# Rauchmelder_2_1.net
KiCad netlist of a schematic drawn in EAGLE
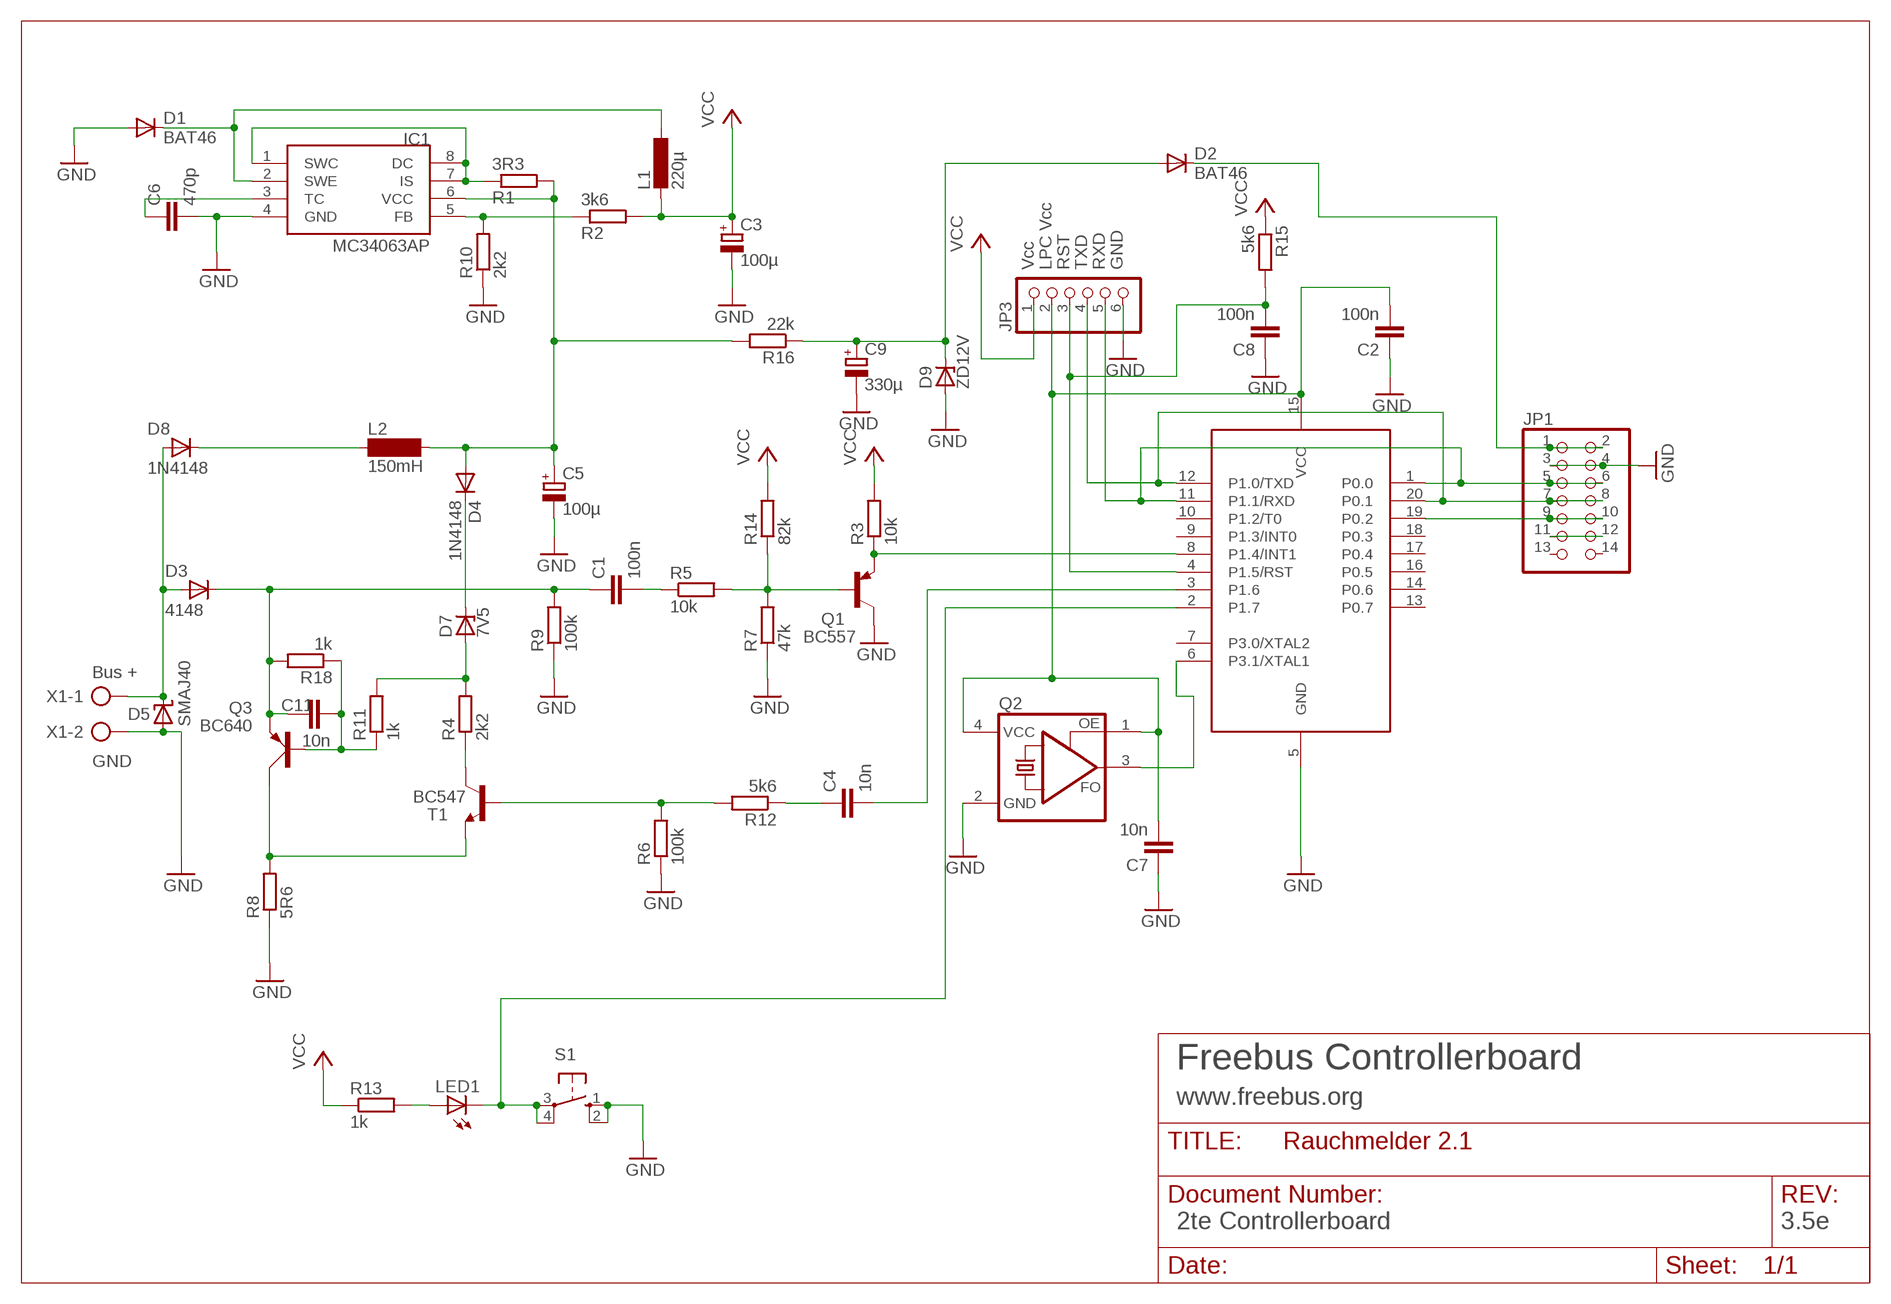
[diagram p0: schematic, sheet 1]

(export (version "E")
  (design (tool "Eeschema 10.0.6"))
  (components
    (comp (ref "89LPC922")
      (value "89LPC922")
      (footprint "eagle-import:DIL20")
      (libsource (lib "eagle-import") (part "89LPC922"))
    )
    (comp (ref "C1")
      (value "100n")
      (footprint "eagle-import:C025-024X044")
      (libsource (lib "eagle-import") (part "C-EU025-024X044"))
    )
    (comp (ref "C2")
      (value "100n")
      (footprint "eagle-import:C025-024X044")
      (libsource (lib "eagle-import") (part "C-EU025-024X044"))
    )
    (comp (ref "C3")
      (value "100µ")
      (footprint "eagle-import:E2,5-6")
      (libsource (lib "eagle-import") (part "CPOL-EUE2.5-6"))
    )
    (comp (ref "C4")
      (value "10n")
      (footprint "eagle-import:C025-024X044")
      (libsource (lib "eagle-import") (part "C-EU025-024X044"))
    )
    (comp (ref "C5")
      (value "100µ")
      (footprint "eagle-import:E3,5-8")
      (libsource (lib "eagle-import") (part "CPOL-EUE3.5-8"))
    )
    (comp (ref "C6")
      (value "470p")
      (footprint "eagle-import:C025-024X044")
      (libsource (lib "eagle-import") (part "C-EU025-024X044"))
    )
    (comp (ref "C7")
      (value "10n")
      (footprint "eagle-import:C1206")
      (libsource (lib "eagle-import") (part "C-EUC1206"))
    )
    (comp (ref "C8")
      (value "100n")
      (footprint "eagle-import:C025-024X044")
      (libsource (lib "eagle-import") (part "C-EU025-024X044"))
    )
    (comp (ref "C9")
      (value "330µ")
      (footprint "eagle-import:E3,5-8")
      (libsource (lib "eagle-import") (part "CPOL-EUE3.5-8"))
    )
    (comp (ref "C11")
      (value "10n")
      (footprint "eagle-import:C025-024X044")
      (libsource (lib "eagle-import") (part "C-EU025-024X044"))
    )
    (comp (ref "D1")
      (value "BAT46")
      (footprint "eagle-import:DO34-7")
      (libsource (lib "eagle-import") (part "BAT81"))
    )
    (comp (ref "D2")
      (value "BAT46")
      (footprint "eagle-import:DO34-7")
      (libsource (lib "eagle-import") (part "BAT81"))
    )
    (comp (ref "D3")
      (value "4148")
      (footprint "eagle-import:DO35-S")
      (libsource (lib "eagle-import") (part "DO35-STEHEND"))
    )
    (comp (ref "D4")
      (value "1N4148")
      (footprint "eagle-import:DO35-10")
      (libsource (lib "eagle-import") (part "1N4148"))
    )
    (comp (ref "D5")
      (value "SMAJ40")
      (footprint "eagle-import:SMBJ")
      (libsource (lib "eagle-import") (part "SUPPRESSOR-SMBJ"))
    )
    (comp (ref "D7")
      (value "7V5")
      (footprint "eagle-import:ZDIO-2.5")
      (libsource (lib "eagle-import") (part "BZX85ZDIOV"))
    )
    (comp (ref "D8")
      (value "1N4148")
      (footprint "eagle-import:DO35-S")
      (libsource (lib "eagle-import") (part "DO35-STEHEND"))
    )
    (comp (ref "D9")
      (value "ZD12V")
      (footprint "eagle-import:DO34Z7")
      (libsource (lib "eagle-import") (part "BZX90"))
    )
    (comp (ref "IC1")
      (value "MC34063AP")
      (footprint "eagle-import:DIL08")
      (libsource (lib "eagle-import") (part "MC34063AP"))
    )
    (comp (ref "JP1")
      (value "PINHD-2X7")
      (footprint "eagle-import:2X07")
      (libsource (lib "eagle-import") (part "PINHD-2X7"))
    )
    (comp (ref "JP3")
      (value "PINHD-1X6")
      (footprint "eagle-import:1X06")
      (libsource (lib "eagle-import") (part "PINHD-1X6"))
    )
    (comp (ref "L1")
      (value "220µ")
      (footprint "eagle-import:0207_12")
      (libsource (lib "eagle-import") (part "L-EU0207/12"))
    )
    (comp (ref "L2")
      (value "150mH")
      (footprint "eagle-import:BS11")
      (libsource (lib "eagle-import") (part "BS11"))
    )
    (comp (ref "LED1")
      (value "LED3MM")
      (footprint "eagle-import:LED3MM")
      (libsource (lib "eagle-import") (part "LED3MM"))
    )
    (comp (ref "Q1")
      (value "BC557")
      (footprint "eagle-import:TO92")
      (libsource (lib "eagle-import") (part "BC557"))
    )
    (comp (ref "Q2")
      (value "ASFL")
      (footprint "eagle-import:ASF")
      (libsource (lib "eagle-import") (part "ASFL"))
    )
    (comp (ref "Q3")
      (value "BC640")
      (footprint "eagle-import:SOT54D")
      (libsource (lib "eagle-import") (part "BC640"))
    )
    (comp (ref "R1")
      (value "3R3")
      (footprint "eagle-import:0207_7")
      (libsource (lib "eagle-import") (part "R-EU_0207/7"))
    )
    (comp (ref "R2")
      (value "3k6")
      (footprint "eagle-import:0207_7")
      (libsource (lib "eagle-import") (part "R-EU_0207/7"))
    )
    (comp (ref "R3")
      (value "10k")
      (footprint "eagle-import:0207_7")
      (libsource (lib "eagle-import") (part "R-EU_0207/7"))
    )
    (comp (ref "R4")
      (value "2k2")
      (footprint "eagle-import:0207_2V")
      (libsource (lib "eagle-import") (part "R-EU_0207/2V"))
    )
    (comp (ref "R5")
      (value "10k")
      (footprint "eagle-import:0207_7")
      (libsource (lib "eagle-import") (part "R-EU_0207/7"))
    )
    (comp (ref "R6")
      (value "100k")
      (footprint "eagle-import:0207_2V")
      (libsource (lib "eagle-import") (part "R-EU_0207/2V"))
    )
    (comp (ref "R7")
      (value "47k")
      (footprint "eagle-import:0207_7")
      (libsource (lib "eagle-import") (part "R-EU_0207/7"))
    )
    (comp (ref "R8")
      (value "5R6")
      (footprint "eagle-import:0207_2V")
      (libsource (lib "eagle-import") (part "R-EU_0207/2V"))
    )
    (comp (ref "R9")
      (value "100k")
      (footprint "eagle-import:0207_7")
      (libsource (lib "eagle-import") (part "R-EU_0207/7"))
    )
    (comp (ref "R10")
      (value "2k2")
      (footprint "eagle-import:0207_7")
      (libsource (lib "eagle-import") (part "R-EU_0207/7"))
    )
    (comp (ref "R11")
      (value "1k")
      (footprint "eagle-import:0207_2V")
      (libsource (lib "eagle-import") (part "R-EU_0207/2V"))
    )
    (comp (ref "R12")
      (value "5k6")
      (footprint "eagle-import:0207_7")
      (libsource (lib "eagle-import") (part "R-EU_0207/7"))
    )
    (comp (ref "R13")
      (value "1k")
      (footprint "eagle-import:0207_7")
      (libsource (lib "eagle-import") (part "R-EU_0207/7"))
    )
    (comp (ref "R14")
      (value "82k")
      (footprint "eagle-import:0207_7")
      (libsource (lib "eagle-import") (part "R-EU_0207/7"))
    )
    (comp (ref "R15")
      (value "5k6")
      (footprint "eagle-import:0207_2V")
      (libsource (lib "eagle-import") (part "R-EU_0207/2V"))
    )
    (comp (ref "R16")
      (value "22k")
      (footprint "eagle-import:0207_2V")
      (libsource (lib "eagle-import") (part "R-EU_0207/2V"))
    )
    (comp (ref "R18")
      (value "1k")
      (footprint "eagle-import:0207_2V")
      (libsource (lib "eagle-import") (part "R-EU_0207/2V"))
    )
    (comp (ref "S1")
      (value "10-XX")
      (footprint "eagle-import:B3F-10XX")
      (libsource (lib "eagle-import") (part "10-XX"))
    )
    (comp (ref "T1")
      (value "BC547")
      (footprint "eagle-import:TO92")
      (libsource (lib "eagle-import") (part "BC547"))
    )
    (comp (ref "X1")
      (value "AK500/2")
      (footprint "eagle-import:AK500_2")
      (libsource (lib "eagle-import") (part "AK500/2"))
    )
  )
  (nets
    (net (code "1") (name "GND") (class "Default")
      (node (ref "89LPC922") (pin "5") (pinfunction "GND_5") (pintype "bidirectional"))
      (node (ref "C2") (pin "1") (pinfunction "1_1") (pintype "passive"))
      (node (ref "C3") (pin "-") (pinfunction "-_-") (pintype "passive"))
      (node (ref "C5") (pin "-") (pinfunction "-_-") (pintype "passive"))
      (node (ref "C6") (pin "2") (pinfunction "2_2") (pintype "passive"))
      (node (ref "C7") (pin "1") (pinfunction "1_1") (pintype "passive"))
      (node (ref "C8") (pin "1") (pinfunction "1_1") (pintype "passive"))
      (node (ref "C9") (pin "-") (pinfunction "-_-") (pintype "passive"))
      (node (ref "D1") (pin "A") (pinfunction "A_A") (pintype "passive"))
      (node (ref "D5") (pin "A") (pinfunction "A_A") (pintype "passive"))
      (node (ref "D9") (pin "A") (pinfunction "A_A") (pintype "passive"))
      (node (ref "IC1") (pin "4") (pinfunction "GND_4") (pintype "passive"))
      (node (ref "JP1") (pin "3") (pinfunction "3_3") (pintype "passive"))
      (node (ref "JP1") (pin "4") (pinfunction "4_4") (pintype "passive"))
      (node (ref "JP3") (pin "6") (pinfunction "6_6") (pintype "passive"))
      (node (ref "Q1") (pin "3") (pinfunction "C_3") (pintype "passive"))
      (node (ref "Q2") (pin "2") (pinfunction "GND_2") (pintype "power_in"))
      (node (ref "R10") (pin "1") (pinfunction "1_1") (pintype "passive"))
      (node (ref "R6") (pin "1") (pinfunction "1_1") (pintype "passive"))
      (node (ref "R7") (pin "1") (pinfunction "1_1") (pintype "passive"))
      (node (ref "R8") (pin "1") (pinfunction "1_1") (pintype "passive"))
      (node (ref "R9") (pin "1") (pinfunction "1_1") (pintype "passive"))
      (node (ref "S1") (pin "1") (pinfunction "S_1") (pintype "passive"))
      (node (ref "S1") (pin "2") (pinfunction "S1_2") (pintype "passive"))
      (node (ref "X1") (pin "2") (pinfunction "KL_2") (pintype "passive"))
    )
    (net (code "2") (name "Net-(89LPC922-P0.0)") (class "Default")
      (node (ref "89LPC922") (pin "1") (pinfunction "P0.0_1") (pintype "bidirectional"))
      (node (ref "89LPC922") (pin "11") (pinfunction "P1.1/RXD_11") (pintype "bidirectional"))
      (node (ref "JP1") (pin "5") (pinfunction "5_5") (pintype "passive"))
      (node (ref "JP1") (pin "6") (pinfunction "6_6") (pintype "passive"))
      (node (ref "JP3") (pin "5") (pinfunction "5_5") (pintype "passive"))
    )
    (net (code "3") (name "Net-(89LPC922-P0.1)") (class "Default")
      (node (ref "89LPC922") (pin "12") (pinfunction "P1.0/TXD_12") (pintype "bidirectional"))
      (node (ref "89LPC922") (pin "20") (pinfunction "P0.1_20") (pintype "bidirectional"))
      (node (ref "JP1") (pin "7") (pinfunction "7_7") (pintype "passive"))
      (node (ref "JP1") (pin "8") (pinfunction "8_8") (pintype "passive"))
      (node (ref "JP3") (pin "4") (pinfunction "4_4") (pintype "passive"))
    )
    (net (code "4") (name "Net-(89LPC922-P0.2)") (class "Default")
      (node (ref "89LPC922") (pin "19") (pinfunction "P0.2_19") (pintype "bidirectional"))
      (node (ref "JP1") (pin "10") (pinfunction "10_10") (pintype "passive"))
      (node (ref "JP1") (pin "9") (pinfunction "9_9") (pintype "passive"))
    )
    (net (code "5") (name "Net-(89LPC922-P1.4{slash}INT1)") (class "Default")
      (node (ref "89LPC922") (pin "8") (pinfunction "P1.4/INT1_8") (pintype "bidirectional"))
      (node (ref "Q1") (pin "1") (pinfunction "E_1") (pintype "passive"))
      (node (ref "R3") (pin "1") (pinfunction "1_1") (pintype "passive"))
    )
    (net (code "6") (name "Net-(89LPC922-P1.5{slash}RST)") (class "Default")
      (node (ref "89LPC922") (pin "4") (pinfunction "P1.5/RST_4") (pintype "bidirectional"))
      (node (ref "C8") (pin "2") (pinfunction "2_2") (pintype "passive"))
      (node (ref "JP3") (pin "3") (pinfunction "3_3") (pintype "passive"))
      (node (ref "R15") (pin "2") (pinfunction "2_2") (pintype "passive"))
    )
    (net (code "7") (name "Net-(89LPC922-P1.6)") (class "Default")
      (node (ref "89LPC922") (pin "3") (pinfunction "P1.6_3") (pintype "bidirectional"))
      (node (ref "C4") (pin "2") (pinfunction "2_2") (pintype "passive"))
    )
    (net (code "8") (name "Net-(89LPC922-P1.7)") (class "Default")
      (node (ref "89LPC922") (pin "2") (pinfunction "P1.7_2") (pintype "bidirectional"))
      (node (ref "LED1") (pin "K") (pinfunction "C_K") (pintype "passive"))
      (node (ref "S1") (pin "3") (pinfunction "P_3") (pintype "passive"))
      (node (ref "S1") (pin "4") (pinfunction "P1_4") (pintype "passive"))
    )
    (net (code "9") (name "Net-(89LPC922-P3.1{slash}XTAL1)") (class "Default")
      (node (ref "89LPC922") (pin "6") (pinfunction "P3.1/XTAL1_6") (pintype "bidirectional"))
      (node (ref "Q2") (pin "3") (pinfunction "FO_3") (pintype "output"))
    )
    (net (code "10") (name "Net-(89LPC922-VCC)") (class "Default")
      (node (ref "89LPC922") (pin "15") (pinfunction "VCC_15") (pintype "bidirectional"))
      (node (ref "C2") (pin "2") (pinfunction "2_2") (pintype "passive"))
      (node (ref "C7") (pin "2") (pinfunction "2_2") (pintype "passive"))
      (node (ref "JP3") (pin "2") (pinfunction "2_2") (pintype "passive"))
      (node (ref "Q2") (pin "1") (pinfunction "OE_1") (pintype "input"))
      (node (ref "Q2") (pin "4") (pinfunction "VCC_4") (pintype "power_in"))
    )
    (net (code "11") (name "Net-(C1-Pad2)") (class "Default")
      (node (ref "C1") (pin "2") (pinfunction "2_2") (pintype "passive"))
      (node (ref "R5") (pin "1") (pinfunction "1_1") (pintype "passive"))
    )
    (net (code "12") (name "Net-(C4-Pad1)") (class "Default")
      (node (ref "C4") (pin "1") (pinfunction "1_1") (pintype "passive"))
      (node (ref "R12") (pin "1") (pinfunction "1_1") (pintype "passive"))
    )
    (net (code "13") (name "Net-(C9-Pad+)") (class "Default")
      (node (ref "C9") (pin "+") (pinfunction "+_+") (pintype "passive"))
      (node (ref "D2") (pin "A") (pinfunction "A_A") (pintype "passive"))
      (node (ref "D9") (pin "C") (pinfunction "C_C") (pintype "passive"))
      (node (ref "R16") (pin "1") (pinfunction "1_1") (pintype "passive"))
    )
    (net (code "14") (name "Net-(C11-Pad2)") (class "Default")
      (node (ref "C11") (pin "2") (pinfunction "2_2") (pintype "passive"))
      (node (ref "Q3") (pin "B") (pinfunction "B_B") (pintype "passive"))
      (node (ref "R11") (pin "1") (pinfunction "1_1") (pintype "passive"))
      (node (ref "R18") (pin "1") (pinfunction "1_1") (pintype "passive"))
    )
    (net (code "15") (name "Net-(D2-PadC)") (class "Default")
      (node (ref "D2") (pin "C") (pinfunction "C_C") (pintype "passive"))
      (node (ref "JP1") (pin "1") (pinfunction "1_1") (pintype "passive"))
      (node (ref "JP1") (pin "2") (pinfunction "2_2") (pintype "passive"))
    )
    (net (code "16") (name "Net-(D3-A)") (class "Default")
      (node (ref "D3") (pin "P$1") (pinfunction "A_P$1") (pintype "passive"))
      (node (ref "D5") (pin "C") (pinfunction "C_C") (pintype "passive"))
      (node (ref "D8") (pin "P$1") (pinfunction "A_P$1") (pintype "passive"))
      (node (ref "X1") (pin "1") (pinfunction "KL_1") (pintype "passive"))
    )
    (net (code "17") (name "Net-(D3-B)") (class "Default")
      (node (ref "C1") (pin "1") (pinfunction "1_1") (pintype "passive"))
      (node (ref "C11") (pin "1") (pinfunction "1_1") (pintype "passive"))
      (node (ref "D3") (pin "P$2") (pinfunction "B_P$2") (pintype "passive"))
      (node (ref "Q3") (pin "E") (pinfunction "E_E") (pintype "passive"))
      (node (ref "R18") (pin "2") (pinfunction "2_2") (pintype "passive"))
      (node (ref "R9") (pin "2") (pinfunction "2_2") (pintype "passive"))
    )
    (net (code "18") (name "Net-(D4-PadC)") (class "Default")
      (node (ref "D4") (pin "C") (pinfunction "C_C") (pintype "passive"))
      (node (ref "D7") (pin "C") (pinfunction "C_C") (pintype "passive"))
    )
    (net (code "19") (name "Net-(D7-PadA)") (class "Default")
      (node (ref "D7") (pin "A") (pinfunction "A_A") (pintype "passive"))
      (node (ref "R11") (pin "2") (pinfunction "2_2") (pintype "passive"))
      (node (ref "R4") (pin "2") (pinfunction "2_2") (pintype "passive"))
    )
    (net (code "20") (name "Net-(D8-B)") (class "Default")
      (node (ref "D8") (pin "P$2") (pinfunction "B_P$2") (pintype "passive"))
      (node (ref "L2") (pin "1") (pinfunction "1_1") (pintype "passive"))
    )
    (net (code "21") (name "Net-(IC1-DC)") (class "Default")
      (node (ref "IC1") (pin "1") (pinfunction "SWC_1") (pintype "passive"))
      (node (ref "IC1") (pin "7") (pinfunction "IS_7") (pintype "passive"))
      (node (ref "IC1") (pin "8") (pinfunction "DC_8") (pintype "passive"))
      (node (ref "R1") (pin "1") (pinfunction "1_1") (pintype "passive"))
    )
    (net (code "22") (name "Net-(IC1-FB)") (class "Default")
      (node (ref "IC1") (pin "5") (pinfunction "FB_5") (pintype "passive"))
      (node (ref "R10") (pin "2") (pinfunction "2_2") (pintype "passive"))
      (node (ref "R2") (pin "1") (pinfunction "1_1") (pintype "passive"))
    )
    (net (code "23") (name "Net-(IC1-SWE)") (class "Default")
      (node (ref "D1") (pin "C") (pinfunction "C_C") (pintype "passive"))
      (node (ref "IC1") (pin "2") (pinfunction "SWE_2") (pintype "passive"))
      (node (ref "L1") (pin "1") (pinfunction "1_1") (pintype "passive"))
    )
    (net (code "24") (name "Net-(IC1-TC)") (class "Default")
      (node (ref "C6") (pin "1") (pinfunction "1_1") (pintype "passive"))
      (node (ref "IC1") (pin "3") (pinfunction "TC_3") (pintype "passive"))
    )
    (net (code "25") (name "Net-(IC1-VCC)") (class "Default")
      (node (ref "C5") (pin "+") (pinfunction "+_+") (pintype "passive"))
      (node (ref "D4") (pin "A") (pinfunction "A_A") (pintype "passive"))
      (node (ref "IC1") (pin "6") (pinfunction "VCC_6") (pintype "passive"))
      (node (ref "L2") (pin "2") (pinfunction "2_2") (pintype "passive"))
      (node (ref "R1") (pin "2") (pinfunction "2_2") (pintype "passive"))
      (node (ref "R16") (pin "2") (pinfunction "2_2") (pintype "passive"))
    )
    (net (code "26") (name "Net-(JP1-Pad11)") (class "Default")
      (node (ref "JP1") (pin "11") (pinfunction "11_11") (pintype "passive"))
      (node (ref "JP1") (pin "12") (pinfunction "12_12") (pintype "passive"))
    )
    (net (code "27") (name "Net-(LED1-PadA)") (class "Default")
      (node (ref "LED1") (pin "A") (pinfunction "A_A") (pintype "passive"))
      (node (ref "R13") (pin "2") (pinfunction "2_2") (pintype "passive"))
    )
    (net (code "28") (name "Net-(Q1-B)") (class "Default")
      (node (ref "Q1") (pin "2") (pinfunction "B_2") (pintype "passive"))
      (node (ref "R14") (pin "1") (pinfunction "1_1") (pintype "passive"))
      (node (ref "R5") (pin "2") (pinfunction "2_2") (pintype "passive"))
      (node (ref "R7") (pin "2") (pinfunction "2_2") (pintype "passive"))
    )
    (net (code "29") (name "Net-(T1-B)") (class "Default")
      (node (ref "R12") (pin "2") (pinfunction "2_2") (pintype "passive"))
      (node (ref "R6") (pin "2") (pinfunction "2_2") (pintype "passive"))
      (node (ref "T1") (pin "2") (pinfunction "B_2") (pintype "passive"))
    )
    (net (code "30") (name "Net-(T1-C)") (class "Default")
      (node (ref "R4") (pin "1") (pinfunction "1_1") (pintype "passive"))
      (node (ref "T1") (pin "3") (pinfunction "C_3") (pintype "passive"))
    )
    (net (code "31") (name "Net-(T1-E)") (class "Default")
      (node (ref "Q3") (pin "C") (pinfunction "C_C") (pintype "passive"))
      (node (ref "R8") (pin "2") (pinfunction "2_2") (pintype "passive"))
      (node (ref "T1") (pin "1") (pinfunction "E_1") (pintype "passive"))
    )
    (net (code "32") (name "VCC") (class "Default")
      (node (ref "C3") (pin "+") (pinfunction "+_+") (pintype "passive"))
      (node (ref "JP3") (pin "1") (pinfunction "1_1") (pintype "passive"))
      (node (ref "L1") (pin "2") (pinfunction "2_2") (pintype "passive"))
      (node (ref "R13") (pin "1") (pinfunction "1_1") (pintype "passive"))
      (node (ref "R14") (pin "2") (pinfunction "2_2") (pintype "passive"))
      (node (ref "R15") (pin "1") (pinfunction "1_1") (pintype "passive"))
      (node (ref "R2") (pin "2") (pinfunction "2_2") (pintype "passive"))
      (node (ref "R3") (pin "2") (pinfunction "2_2") (pintype "passive"))
    )
    (net (code "33") (name "unconnected-(89LPC922-P0.3-Pad18)") (class "Default")
      (node (ref "89LPC922") (pin "18") (pinfunction "P0.3_18") (pintype "bidirectional"))
    )
    (net (code "34") (name "unconnected-(89LPC922-P0.4-Pad17)") (class "Default")
      (node (ref "89LPC922") (pin "17") (pinfunction "P0.4_17") (pintype "bidirectional"))
    )
    (net (code "35") (name "unconnected-(89LPC922-P0.5-Pad16)") (class "Default")
      (node (ref "89LPC922") (pin "16") (pinfunction "P0.5_16") (pintype "bidirectional"))
    )
    (net (code "36") (name "unconnected-(89LPC922-P0.6-Pad14)") (class "Default")
      (node (ref "89LPC922") (pin "14") (pinfunction "P0.6_14") (pintype "bidirectional"))
    )
    (net (code "37") (name "unconnected-(89LPC922-P0.7-Pad13)") (class "Default")
      (node (ref "89LPC922") (pin "13") (pinfunction "P0.7_13") (pintype "bidirectional"))
    )
    (net (code "38") (name "unconnected-(89LPC922-P1.2{slash}T0-Pad10)") (class "Default")
      (node (ref "89LPC922") (pin "10") (pinfunction "P1.2/T0_10") (pintype "bidirectional"))
    )
    (net (code "39") (name "unconnected-(89LPC922-P1.3{slash}INT0-Pad9)") (class "Default")
      (node (ref "89LPC922") (pin "9") (pinfunction "P1.3/INT0_9") (pintype "bidirectional"))
    )
    (net (code "40") (name "unconnected-(89LPC922-P3.0{slash}XTAL2-Pad7)") (class "Default")
      (node (ref "89LPC922") (pin "7") (pinfunction "P3.0/XTAL2_7") (pintype "bidirectional"))
    )
    (net (code "41") (name "unconnected-(JP1-Pad13)") (class "Default")
      (node (ref "JP1") (pin "13") (pinfunction "13_13") (pintype "passive"))
    )
    (net (code "42") (name "unconnected-(JP1-Pad14)") (class "Default")
      (node (ref "JP1") (pin "14") (pinfunction "14_14") (pintype "passive"))
    )
  )
)
